# BTS7970.net
KiCad netlist of a schematic drawn in Altium Designer
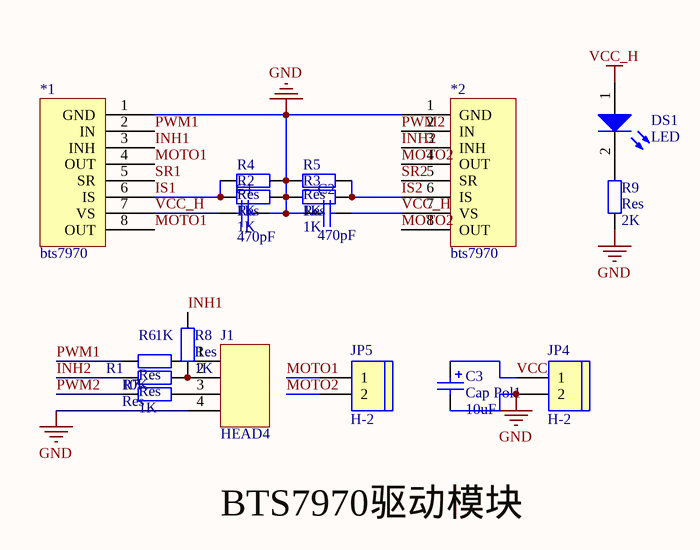
[diagram p0: BTS7970.SchDoc]

(export (version "E")
  (design (tool "Eeschema 10.0.6"))
  (components
    (comp (ref "*1") (value "bts7970") (footprint "bts7970") (libsource (lib "") (part "bts7970_1")))
    (comp (ref "*2") (value "bts7970") (footprint "bts7970") (libsource (lib "HGH") (part "bts7970")))
    (comp (ref "C1")
      (value "470pF")
      (footprint "CC1005-0402")
      (description "Capacitor")
      (fields
        (field (name "MANUFACTURER") "Generic Components")
        (field (name "Comment") "CAP")
        (field (name "PUBLISHER") "Altium Hobart Technology Centre")
      )
      (libsource (lib "HGH") (part "CAP"))
    )
    (comp (ref "C2")
      (value "470pF")
      (footprint "CC1005-0402")
      (description "Capacitor")
      (fields
        (field (name "MANUFACTURER") "Generic Components")
        (field (name "Comment") "CAP")
        (field (name "PUBLISHER") "Altium Hobart Technology Centre")
      )
      (libsource (lib "HGH") (part "CAP"))
    )
    (comp (ref "C3")
      (value "Cap Pol1")
      (footprint "RB0.15-0.32")
      (description "Polarized Capacitor (Radial)")
      (fields
        (field (name "MANUFACTURER") "Generic Components")
        (field (name "ALTIUM_VALUE") "10uF")
        (field (name "PUBLISHER") "Altium Hobart Technology Centre")
      )
      (libsource (lib "HGH") (part "Cap Pol1"))
    )
    (comp (ref "DS1")
      (value "LED")
      (footprint "LED0.1-0.22")
      (description "Typical RED, GREEN, YELLOW, AMBER GaAs LED")
      (fields
        (field (name "MANUFACTURER") "Generic Components")
        (field (name "PUBLISHER") "Altium Hobart Technology Centre")
      )
      (libsource (lib "HGH") (part "LED"))
    )
    (comp (ref "J1")
      (value "HEAD4")
      (footprint "HDR1-4")
      (description "Connector,4-pin")
      (libsource (lib "HGH") (part "HEAD4"))
    )
    (comp (ref "JP4")
      (value "H-2")
      (footprint "H-2/2-T")
      (description "Header, 2-Pin")
      (fields (field (name "MANUFACTURER") "Generic Components"))
      (libsource (lib "HGH") (part "H-2"))
    )
    (comp (ref "JP5")
      (value "H-2")
      (footprint "H-2/2-T")
      (description "Header, 2-Pin")
      (fields (field (name "MANUFACTURER") "Generic Components"))
      (libsource (lib "HGH") (part "H-2"))
    )
    (comp (ref "R1")
      (value "Res")
      (footprint "R2012-0805")
      (description "Resistor")
      (fields
        (field (name "MANUFACTURER") "Generic Components")
        (field (name "ALTIUM_VALUE") "1K")
        (field (name "PUBLISHER") "Altium Hobart Technology Centre")
      )
      (libsource (lib "HGH") (part "Res"))
    )
    (comp (ref "R2")
      (value "Res")
      (footprint "R2012-0805")
      (description "Resistor")
      (fields
        (field (name "MANUFACTURER") "Generic Components")
        (field (name "ALTIUM_VALUE") "1K")
        (field (name "PUBLISHER") "Altium Hobart Technology Centre")
      )
      (libsource (lib "HGH") (part "Res"))
    )
    (comp (ref "R3")
      (value "Res")
      (footprint "R2012-0805")
      (description "Resistor")
      (fields
        (field (name "MANUFACTURER") "Generic Components")
        (field (name "ALTIUM_VALUE") "1K")
        (field (name "PUBLISHER") "Altium Hobart Technology Centre")
      )
      (libsource (lib "HGH") (part "Res"))
    )
    (comp (ref "R4")
      (value "Res")
      (footprint "R2012-0805")
      (description "Resistor")
      (fields
        (field (name "MANUFACTURER") "Generic Components")
        (field (name "ALTIUM_VALUE") "1K")
        (field (name "PUBLISHER") "Altium Hobart Technology Centre")
      )
      (libsource (lib "HGH") (part "Res"))
    )
    (comp (ref "R5")
      (value "Res")
      (footprint "R2012-0805")
      (description "Resistor")
      (fields
        (field (name "MANUFACTURER") "Generic Components")
        (field (name "ALTIUM_VALUE") "1K")
        (field (name "PUBLISHER") "Altium Hobart Technology Centre")
      )
      (libsource (lib "HGH") (part "Res"))
    )
    (comp (ref "R6")
      (value "Res")
      (footprint "R2012-0805")
      (description "Resistor")
      (fields
        (field (name "MANUFACTURER") "Generic Components")
        (field (name "ALTIUM_VALUE") "1K")
        (field (name "PUBLISHER") "Altium Hobart Technology Centre")
      )
      (libsource (lib "HGH") (part "Res"))
    )
    (comp (ref "R7")
      (value "Res")
      (footprint "R2012-0805")
      (description "Resistor")
      (fields
        (field (name "MANUFACTURER") "Generic Components")
        (field (name "ALTIUM_VALUE") "10K")
        (field (name "PUBLISHER") "Altium Hobart Technology Centre")
      )
      (libsource (lib "HGH") (part "Res"))
    )
    (comp (ref "R8")
      (value "Res")
      (footprint "R2012-0805")
      (description "Resistor")
      (fields
        (field (name "MANUFACTURER") "Generic Components")
        (field (name "ALTIUM_VALUE") "1K")
        (field (name "PUBLISHER") "Altium Hobart Technology Centre")
      )
      (libsource (lib "") (part "Res_1"))
    )
    (comp (ref "R9")
      (value "Res")
      (footprint "R2012-0805")
      (description "Resistor")
      (fields
        (field (name "MANUFACTURER") "Generic Components")
        (field (name "ALTIUM_VALUE") "2K")
        (field (name "PUBLISHER") "Altium Hobart Technology Centre")
      )
      (libsource (lib "") (part "Res_1"))
    )
  )
  (nets
    (net (code "2") (name "/INH1") (class "Default")
      (node (ref "*1") (pin "3") (pinfunction "INH_3") (pintype "passive"))
      (node (ref "R8") (pin "2") (pinfunction "2_2") (pintype "passive"))
    )
    (net (code "3") (name "/INH2") (class "Default")
      (node (ref "*2") (pin "3") (pinfunction "INH_3") (pintype "passive"))
      (node (ref "R1") (pin "2") (pinfunction "2_2") (pintype "passive"))
    )
    (net (code "4") (name "/IS1") (class "Default")
      (node (ref "*1") (pin "6") (pinfunction "IS_6") (pintype "passive"))
      (node (ref "R2") (pin "2") (pinfunction "2_2") (pintype "passive"))
      (node (ref "R4") (pin "2") (pinfunction "2_2") (pintype "passive"))
    )
    (net (code "5") (name "/IS2") (class "Default")
      (node (ref "*2") (pin "6") (pinfunction "IS_6") (pintype "passive"))
      (node (ref "R3") (pin "1") (pinfunction "1_1") (pintype "passive"))
      (node (ref "R5") (pin "1") (pinfunction "1_1") (pintype "passive"))
    )
    (net (code "6") (name "/MOTO1") (class "Default")
      (node (ref "*1") (pin "4") (pinfunction "OUT_4") (pintype "passive"))
      (node (ref "*1") (pin "8") (pinfunction "OUT_8") (pintype "passive"))
      (node (ref "JP5") (pin "1") (pinfunction "1_1") (pintype "passive"))
    )
    (net (code "7") (name "/MOTO2") (class "Default")
      (node (ref "*2") (pin "4") (pinfunction "OUT_4") (pintype "passive"))
      (node (ref "*2") (pin "8") (pinfunction "OUT_8") (pintype "passive"))
      (node (ref "JP5") (pin "2") (pinfunction "2_2") (pintype "passive"))
    )
    (net (code "8") (name "/PWM1") (class "Default")
      (node (ref "*1") (pin "2") (pinfunction "IN_2") (pintype "passive"))
      (node (ref "R6") (pin "2") (pinfunction "2_2") (pintype "passive"))
    )
    (net (code "9") (name "/PWM2") (class "Default")
      (node (ref "*2") (pin "2") (pinfunction "IN_2") (pintype "passive"))
      (node (ref "R7") (pin "2") (pinfunction "2_2") (pintype "passive"))
    )
    (net (code "10") (name "/SR1") (class "Default")
      (node (ref "*1") (pin "5") (pinfunction "SR_5") (pintype "passive"))
    )
    (net (code "11") (name "/SR2") (class "Default")
      (node (ref "*2") (pin "5") (pinfunction "SR_5") (pintype "passive"))
    )
    (net (code "12") (name "GND") (class "Default")
      (node (ref "*1") (pin "1") (pinfunction "GND_1") (pintype "passive"))
      (node (ref "*2") (pin "1") (pinfunction "GND_1") (pintype "passive"))
      (node (ref "C1") (pin "2") (pinfunction "2_2") (pintype "passive"))
      (node (ref "C2") (pin "1") (pinfunction "1_1") (pintype "passive"))
      (node (ref "C3") (pin "2") (pinfunction "2_2") (pintype "passive"))
      (node (ref "J1") (pin "4") (pinfunction "4_4") (pintype "passive"))
      (node (ref "JP4") (pin "2") (pinfunction "2_2") (pintype "passive"))
      (node (ref "R2") (pin "1") (pinfunction "1_1") (pintype "passive"))
      (node (ref "R3") (pin "2") (pinfunction "2_2") (pintype "passive"))
      (node (ref "R4") (pin "1") (pinfunction "1_1") (pintype "passive"))
      (node (ref "R5") (pin "2") (pinfunction "2_2") (pintype "passive"))
      (node (ref "R9") (pin "1") (pinfunction "1_1") (pintype "passive"))
    )
    (net (code "13") (name "Net-(DS1-K)") (class "Default")
      (node (ref "DS1") (pin "2") (pinfunction "K_2") (pintype "passive"))
      (node (ref "R9") (pin "2") (pinfunction "2_2") (pintype "passive"))
    )
    (net (code "14") (name "Net-(J1-Pad1)") (class "Default")
      (node (ref "J1") (pin "1") (pinfunction "1_1") (pintype "passive"))
      (node (ref "R6") (pin "1") (pinfunction "1_1") (pintype "passive"))
    )
    (net (code "15") (name "Net-(J1-Pad2)") (class "Default")
      (node (ref "J1") (pin "2") (pinfunction "2_2") (pintype "passive"))
      (node (ref "R1") (pin "1") (pinfunction "1_1") (pintype "passive"))
      (node (ref "R8") (pin "1") (pinfunction "1_1") (pintype "passive"))
    )
    (net (code "16") (name "Net-(J1-Pad3)") (class "Default")
      (node (ref "J1") (pin "3") (pinfunction "3_3") (pintype "passive"))
      (node (ref "R7") (pin "1") (pinfunction "1_1") (pintype "passive"))
    )
    (net (code "17") (name "VCC_H") (class "Default")
      (node (ref "*1") (pin "7") (pinfunction "VS_7") (pintype "passive"))
      (node (ref "*2") (pin "7") (pinfunction "VS_7") (pintype "passive"))
      (node (ref "C1") (pin "1") (pinfunction "1_1") (pintype "passive"))
      (node (ref "C2") (pin "2") (pinfunction "2_2") (pintype "passive"))
      (node (ref "C3") (pin "1") (pinfunction "1_1") (pintype "passive"))
      (node (ref "DS1") (pin "1") (pinfunction "A_1") (pintype "passive"))
      (node (ref "JP4") (pin "1") (pinfunction "1_1") (pintype "passive"))
    )
  )
)
